# uDiplexer_v1.net
KiCad netlist of a schematic drawn in EAGLE
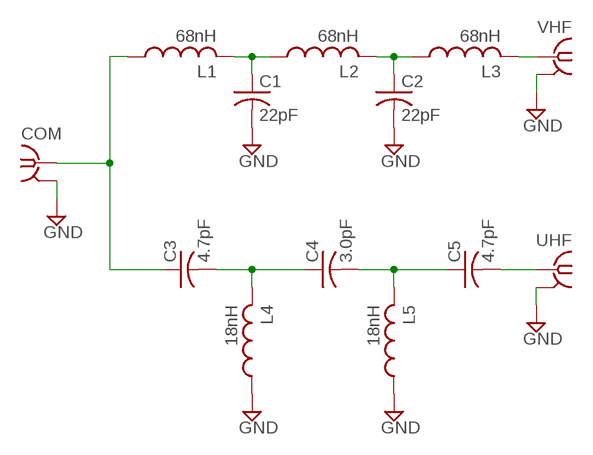
[diagram p0: schematic, sheet 1]

(export (version "E")
  (design (tool "Eeschema 10.0.6"))
  (components
    (comp (ref "C1")
      (value "22pF")
      (footprint "eagle-import:C0805K")
      (libsource (lib "eagle-import") (part "C-USC0805K"))
    )
    (comp (ref "C2")
      (value "22pF")
      (footprint "eagle-import:C0805K")
      (libsource (lib "eagle-import") (part "C-USC0805K"))
    )
    (comp (ref "C3")
      (value "4.7pF")
      (footprint "eagle-import:C0805K")
      (libsource (lib "eagle-import") (part "C-USC0805K"))
    )
    (comp (ref "C4")
      (value "3.0pF")
      (footprint "eagle-import:C0805K")
      (libsource (lib "eagle-import") (part "C-USC0805K"))
    )
    (comp (ref "C5")
      (value "4.7pF")
      (footprint "eagle-import:C0805K")
      (libsource (lib "eagle-import") (part "C-USC0805K"))
    )
    (comp (ref "COM")
      (value "SMA-142-0711-821/826")
      (footprint "eagle-import:J502-ND-142-0711-821_826")
      (fields (field (name "MF") "JOHNSON COMPONENTS") (field (name "MPN") "142-0711-821"))
      (libsource (lib "eagle-import") (part "SMA-142-0711-821/826"))
    )
    (comp (ref "L1")
      (value "68nH")
      (footprint "eagle-import:C0805K")
      (libsource (lib "eagle-import") (part "L-US0805K"))
    )
    (comp (ref "L2")
      (value "68nH")
      (footprint "eagle-import:C0805K")
      (libsource (lib "eagle-import") (part "L-US0805K"))
    )
    (comp (ref "L3")
      (value "68nH")
      (footprint "eagle-import:C0805K")
      (libsource (lib "eagle-import") (part "L-US0805K"))
    )
    (comp (ref "L4")
      (value "18nH")
      (footprint "eagle-import:C0805K")
      (libsource (lib "eagle-import") (part "L-US0805K"))
    )
    (comp (ref "L5")
      (value "18nH")
      (footprint "eagle-import:C0805K")
      (libsource (lib "eagle-import") (part "L-US0805K"))
    )
    (comp (ref "UHF")
      (value "SMA-142-0711-821/826")
      (footprint "eagle-import:J502-ND-142-0711-821_826")
      (fields (field (name "MF") "JOHNSON COMPONENTS") (field (name "MPN") "142-0711-821"))
      (libsource (lib "eagle-import") (part "SMA-142-0711-821/826"))
    )
    (comp (ref "VHF")
      (value "SMA-142-0711-821/826")
      (footprint "eagle-import:J502-ND-142-0711-821_826")
      (fields (field (name "MF") "JOHNSON COMPONENTS") (field (name "MPN") "142-0711-821"))
      (libsource (lib "eagle-import") (part "SMA-142-0711-821/826"))
    )
  )
  (nets
    (net (code "1") (name "GND") (class "Default")
      (node (ref "C1") (pin "2") (pinfunction "2_2") (pintype "passive"))
      (node (ref "C2") (pin "2") (pinfunction "2_2") (pintype "passive"))
      (node (ref "COM") (pin "G@1") (pinfunction "2_G@1") (pintype "passive"))
      (node (ref "COM") (pin "G@2") (pinfunction "2_G@2") (pintype "passive"))
      (node (ref "COM") (pin "G@3") (pinfunction "2_G@3") (pintype "passive"))
      (node (ref "COM") (pin "G@4") (pinfunction "2_G@4") (pintype "passive"))
      (node (ref "L4") (pin "1") (pinfunction "1_1") (pintype "passive"))
      (node (ref "L5") (pin "1") (pinfunction "1_1") (pintype "passive"))
      (node (ref "UHF") (pin "G@1") (pinfunction "2_G@1") (pintype "passive"))
      (node (ref "UHF") (pin "G@2") (pinfunction "2_G@2") (pintype "passive"))
      (node (ref "UHF") (pin "G@3") (pinfunction "2_G@3") (pintype "passive"))
      (node (ref "UHF") (pin "G@4") (pinfunction "2_G@4") (pintype "passive"))
      (node (ref "VHF") (pin "G@1") (pinfunction "2_G@1") (pintype "passive"))
      (node (ref "VHF") (pin "G@2") (pinfunction "2_G@2") (pintype "passive"))
      (node (ref "VHF") (pin "G@3") (pinfunction "2_G@3") (pintype "passive"))
      (node (ref "VHF") (pin "G@4") (pinfunction "2_G@4") (pintype "passive"))
    )
    (net (code "2") (name "Net-(C1-Pad1)") (class "Default")
      (node (ref "C1") (pin "1") (pinfunction "1_1") (pintype "passive"))
      (node (ref "L1") (pin "2") (pinfunction "2_2") (pintype "passive"))
      (node (ref "L2") (pin "1") (pinfunction "1_1") (pintype "passive"))
    )
    (net (code "3") (name "Net-(C2-Pad1)") (class "Default")
      (node (ref "C2") (pin "1") (pinfunction "1_1") (pintype "passive"))
      (node (ref "L2") (pin "2") (pinfunction "2_2") (pintype "passive"))
      (node (ref "L3") (pin "1") (pinfunction "1_1") (pintype "passive"))
    )
    (net (code "4") (name "Net-(C3-Pad1)") (class "Default")
      (node (ref "C3") (pin "1") (pinfunction "1_1") (pintype "passive"))
      (node (ref "COM") (pin "1") (pinfunction "1_1") (pintype "passive"))
      (node (ref "L1") (pin "1") (pinfunction "1_1") (pintype "passive"))
    )
    (net (code "5") (name "Net-(C3-Pad2)") (class "Default")
      (node (ref "C3") (pin "2") (pinfunction "2_2") (pintype "passive"))
      (node (ref "C4") (pin "1") (pinfunction "1_1") (pintype "passive"))
      (node (ref "L4") (pin "2") (pinfunction "2_2") (pintype "passive"))
    )
    (net (code "6") (name "Net-(C4-Pad2)") (class "Default")
      (node (ref "C4") (pin "2") (pinfunction "2_2") (pintype "passive"))
      (node (ref "C5") (pin "1") (pinfunction "1_1") (pintype "passive"))
      (node (ref "L5") (pin "2") (pinfunction "2_2") (pintype "passive"))
    )
    (net (code "7") (name "Net-(C5-Pad2)") (class "Default")
      (node (ref "C5") (pin "2") (pinfunction "2_2") (pintype "passive"))
      (node (ref "UHF") (pin "1") (pinfunction "1_1") (pintype "passive"))
    )
    (net (code "8") (name "Net-(L3-Pad2)") (class "Default")
      (node (ref "L3") (pin "2") (pinfunction "2_2") (pintype "passive"))
      (node (ref "VHF") (pin "1") (pinfunction "1_1") (pintype "passive"))
    )
  )
)
